# nguyenly.net
KiCad netlist of a schematic drawn in Altium Designer
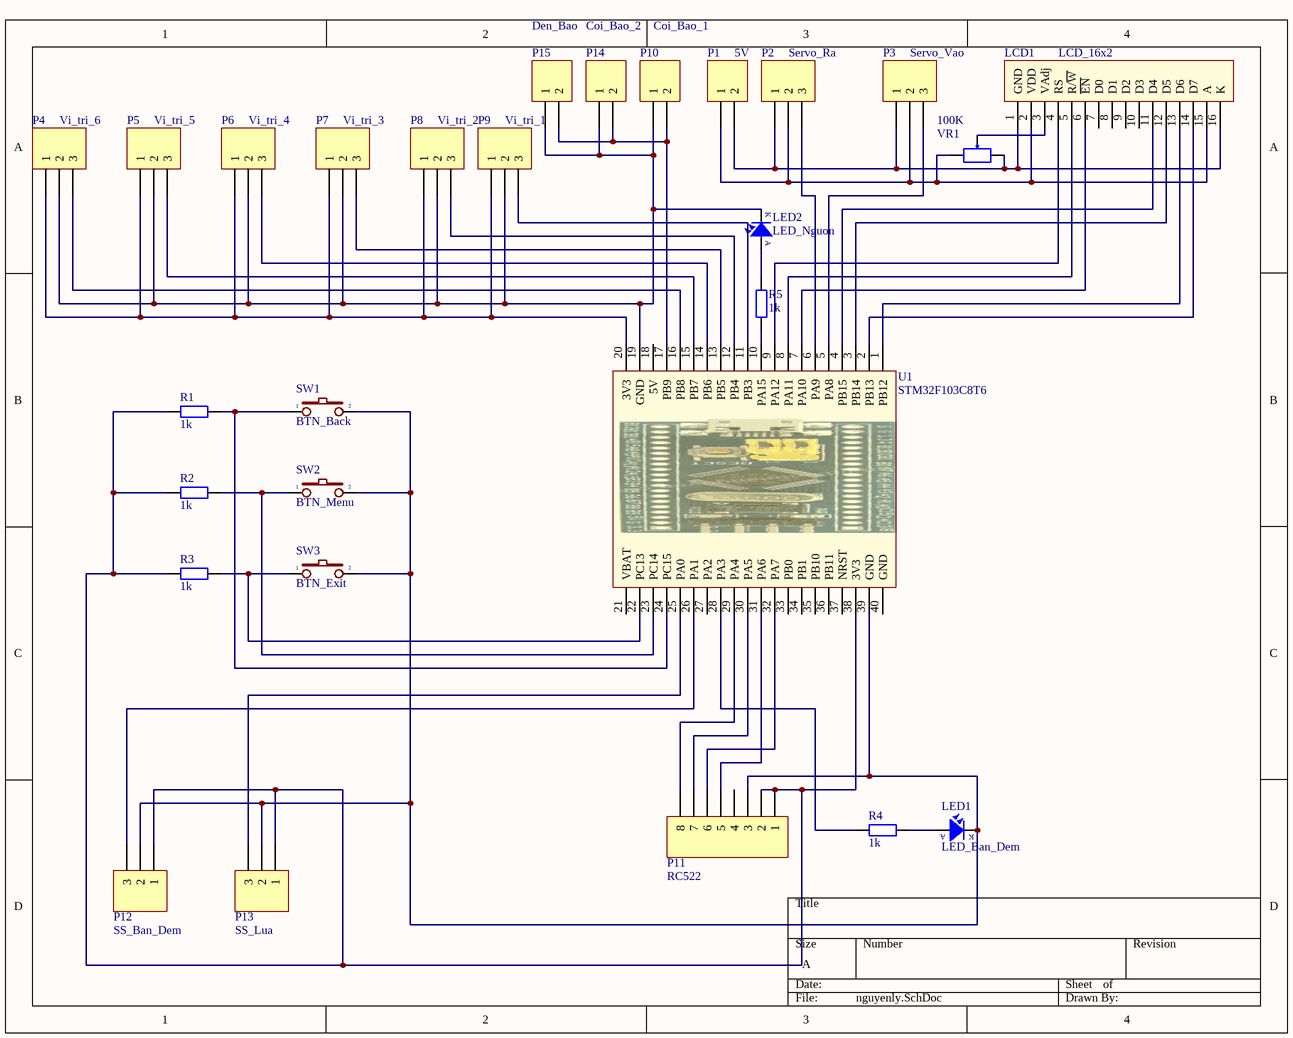
[diagram p0: nguyenly.SchDoc]

(export (version "E")
  (design (tool "Eeschema 10.0.6"))
  (components
    (comp (ref "LCD1")
      (value "LCD_16x2")
      (footprint "LCD16X2")
      (description "LCD dipslay 16 char, 2 line")
      (libsource (lib "Thu vien Altium") (part "LCD16x2"))
    )
    (comp (ref "LED1")
      (value "LED_Ban_Dem")
      (footprint "LED-5")
      (description "LED Single colour Green and Red")
      (libsource (lib "Thu vien Altium") (part "LED"))
    )
    (comp (ref "LED2")
      (value "LED_Nguon")
      (footprint "LED-5")
      (description "LED Single colour Green and Red")
      (libsource (lib "Thu vien Altium") (part "LED"))
    )
    (comp (ref "P1")
      (value "5V")
      (footprint "HDR1X2")
      (description "Header, 2-Pin")
      (fields (field (name "PUBLISHER") "Altium Limited"))
      (libsource (lib "Miscellaneous Connectors") (part "Header 2"))
    )
    (comp (ref "P2")
      (value "Servo_Ra")
      (footprint "HDR1X3")
      (description "Header, 3-Pin")
      (fields (field (name "PUBLISHER") "Altium Limited"))
      (libsource (lib "Miscellaneous Connectors") (part "Header 3"))
    )
    (comp (ref "P3")
      (value "Servo_Vao")
      (footprint "HDR1X3")
      (description "Header, 3-Pin")
      (fields (field (name "PUBLISHER") "Altium Limited"))
      (libsource (lib "Miscellaneous Connectors") (part "Header 3"))
    )
    (comp (ref "P4")
      (value "Vi_tri_6")
      (footprint "HDR1X3")
      (description "Header, 3-Pin")
      (fields (field (name "PUBLISHER") "Altium Limited"))
      (libsource (lib "Miscellaneous Connectors") (part "Header 3"))
    )
    (comp (ref "P5")
      (value "Vi_tri_5")
      (footprint "HDR1X3")
      (description "Header, 3-Pin")
      (fields (field (name "PUBLISHER") "Altium Limited"))
      (libsource (lib "Miscellaneous Connectors") (part "Header 3"))
    )
    (comp (ref "P6")
      (value "Vi_tri_4")
      (footprint "HDR1X3")
      (description "Header, 3-Pin")
      (fields (field (name "PUBLISHER") "Altium Limited"))
      (libsource (lib "Miscellaneous Connectors") (part "Header 3"))
    )
    (comp (ref "P7")
      (value "Vi_tri_3")
      (footprint "HDR1X3")
      (description "Header, 3-Pin")
      (fields (field (name "PUBLISHER") "Altium Limited"))
      (libsource (lib "Miscellaneous Connectors") (part "Header 3"))
    )
    (comp (ref "P8")
      (value "Vi_tri_2")
      (footprint "HDR1X3")
      (description "Header, 3-Pin")
      (fields (field (name "PUBLISHER") "Altium Limited"))
      (libsource (lib "Miscellaneous Connectors") (part "Header 3"))
    )
    (comp (ref "P9")
      (value "Vi_tri_1")
      (footprint "HDR1X3")
      (description "Header, 3-Pin")
      (fields (field (name "PUBLISHER") "Altium Limited"))
      (libsource (lib "Miscellaneous Connectors") (part "Header 3"))
    )
    (comp (ref "P10")
      (value "Coi_Bao_1")
      (footprint "HDR1X2")
      (description "Header, 2-Pin")
      (fields (field (name "PUBLISHER") "Altium Limited"))
      (libsource (lib "Miscellaneous Connectors") (part "Header 2"))
    )
    (comp (ref "P11")
      (value "RC522")
      (footprint "HDR1X8")
      (description "Header, 8-Pin")
      (fields (field (name "PUBLISHER") "Altium Limited"))
      (libsource (lib "Miscellaneous Connectors") (part "Header 8"))
    )
    (comp (ref "P12")
      (value "SS_Ban_Dem")
      (footprint "HDR1X3")
      (description "Header, 3-Pin")
      (fields (field (name "PUBLISHER") "Altium Limited"))
      (libsource (lib "") (part "Header 3_1"))
    )
    (comp (ref "P13")
      (value "SS_Lua")
      (footprint "HDR1X3")
      (description "Header, 3-Pin")
      (fields (field (name "PUBLISHER") "Altium Limited"))
      (libsource (lib "") (part "Header 3_1"))
    )
    (comp (ref "P14")
      (value "Coi_Bao_2")
      (footprint "HDR1X2")
      (description "Header, 2-Pin")
      (fields (field (name "PUBLISHER") "Altium Limited"))
      (libsource (lib "Miscellaneous Connectors") (part "Header 2"))
    )
    (comp (ref "P15")
      (value "Den_Bao")
      (footprint "HDR1X2")
      (description "Header, 2-Pin")
      (fields (field (name "PUBLISHER") "Altium Limited"))
      (libsource (lib "Miscellaneous Connectors") (part "Header 2"))
    )
    (comp (ref "R1")
      (value "1k")
      (footprint "R1/4W")
      (description "Resistor 1/4W")
      (libsource (lib "Thu vien Altium") (part "R1/4W"))
    )
    (comp (ref "R2")
      (value "1k")
      (footprint "R1/4W")
      (description "Resistor 1/4W")
      (libsource (lib "Thu vien Altium") (part "R1/4W"))
    )
    (comp (ref "R3")
      (value "1k")
      (footprint "R1/4W")
      (description "Resistor 1/4W")
      (libsource (lib "Thu vien Altium") (part "R1/4W"))
    )
    (comp (ref "R4")
      (value "1k")
      (footprint "R1/4W")
      (description "Resistor 1/4W")
      (libsource (lib "Thu vien Altium") (part "R1/4W"))
    )
    (comp (ref "R5")
      (value "1k")
      (footprint "R1/4W")
      (description "Resistor 1/4W")
      (libsource (lib "Thu vien Altium") (part "R1/4W"))
    )
    (comp (ref "SW1")
      (value "BTN_Back")
      (footprint "SW2")
      (description "Switch button 2 pin")
      (libsource (lib "Thu vien Altium") (part "SW2"))
    )
    (comp (ref "SW2")
      (value "BTN_Menu")
      (footprint "SW2")
      (description "Switch button 2 pin")
      (libsource (lib "Thu vien Altium") (part "SW2"))
    )
    (comp (ref "SW3")
      (value "BTN_Exit")
      (footprint "SW2")
      (description "Switch button 2 pin")
      (libsource (lib "Thu vien Altium") (part "SW2"))
    )
    (comp (ref "U1")
      (value "STM32F103C8T6")
      (footprint "STM32L103C8_mini")
      (description "STM32F103C8T6 Mini Board")
      (libsource (lib "Thu vien Altium") (part "STM32L103C8_mini"))
    )
    (comp (ref "VR1")
      (value "100K")
      (footprint "VR")
      (description "Var Resistor")
      (libsource (lib "Thu vien Altium") (part "VR"))
    )
  )
  (nets
    (net (code "1") (name "Net-(LCD1-A)") (class "Default")
      (node (ref "LCD1") (pin "15") (pinfunction "A_15") (pintype "passive"))
      (node (ref "LCD1") (pin "2") (pinfunction "VDD_2") (pintype "passive"))
      (node (ref "P1") (pin "1") (pinfunction "1_1") (pintype "passive"))
      (node (ref "P2") (pin "2") (pinfunction "2_2") (pintype "passive"))
      (node (ref "P3") (pin "2") (pinfunction "2_2") (pintype "passive"))
      (node (ref "VR1") (pin "1") (pinfunction "1_1") (pintype "passive"))
    )
    (net (code "2") (name "Net-(LCD1-D4)") (class "Default")
      (node (ref "LCD1") (pin "11") (pinfunction "D4_11") (pintype "passive"))
      (node (ref "U1") (pin "4") (pinfunction "PB15_4") (pintype "passive"))
    )
    (net (code "3") (name "Net-(LCD1-D5)") (class "Default")
      (node (ref "LCD1") (pin "12") (pinfunction "D5_12") (pintype "passive"))
      (node (ref "U1") (pin "3") (pinfunction "PB14_3") (pintype "passive"))
    )
    (net (code "4") (name "Net-(LCD1-D6)") (class "Default")
      (node (ref "LCD1") (pin "13") (pinfunction "D6_13") (pintype "passive"))
      (node (ref "U1") (pin "1") (pinfunction "PB12_1") (pintype "passive"))
    )
    (net (code "5") (name "Net-(LCD1-D7)") (class "Default")
      (node (ref "LCD1") (pin "14") (pinfunction "D7_14") (pintype "passive"))
      (node (ref "U1") (pin "2") (pinfunction "PB13_2") (pintype "passive"))
    )
    (net (code "6") (name "Net-(LCD1-GND)") (class "Default")
      (node (ref "LCD1") (pin "1") (pinfunction "GND_1") (pintype "passive"))
      (node (ref "LCD1") (pin "16") (pinfunction "K_16") (pintype "passive"))
      (node (ref "P1") (pin "2") (pinfunction "2_2") (pintype "passive"))
      (node (ref "P2") (pin "1") (pinfunction "1_1") (pintype "passive"))
      (node (ref "P3") (pin "1") (pinfunction "1_1") (pintype "passive"))
      (node (ref "VR1") (pin "3") (pinfunction "3_3") (pintype "passive"))
    )
    (net (code "7") (name "Net-(LCD1-RS)") (class "Default")
      (node (ref "LCD1") (pin "4") (pinfunction "RS_4") (pintype "passive"))
      (node (ref "U1") (pin "9") (pinfunction "PA12_9") (pintype "passive"))
    )
    (net (code "8") (name "Net-(LCD1-R{slash}~{W})") (class "Default")
      (node (ref "LCD1") (pin "5") (pinfunction "R/~{W}_5") (pintype "passive"))
      (node (ref "U1") (pin "8") (pinfunction "PA11_8") (pintype "passive"))
    )
    (net (code "9") (name "Net-(LCD1-VAdj)") (class "Default")
      (node (ref "LCD1") (pin "3") (pinfunction "VAdj_3") (pintype "passive"))
      (node (ref "VR1") (pin "2") (pinfunction "2_2") (pintype "passive"))
    )
    (net (code "10") (name "Net-(LCD1-~{EN})") (class "Default")
      (node (ref "LCD1") (pin "6") (pinfunction "~{EN}_6") (pintype "passive"))
      (node (ref "U1") (pin "7") (pinfunction "PA10_7") (pintype "passive"))
    )
    (net (code "11") (name "Net-(LED1-A)") (class "Default")
      (node (ref "LED1") (pin "1") (pinfunction "A_1") (pintype "passive"))
      (node (ref "R4") (pin "2") (pinfunction "2_2") (pintype "passive"))
    )
    (net (code "12") (name "Net-(LED1-K)") (class "Default")
      (node (ref "LED1") (pin "2") (pinfunction "K_2") (pintype "passive"))
      (node (ref "P11") (pin "3") (pinfunction "3_3") (pintype "passive"))
      (node (ref "P12") (pin "2") (pinfunction "2_2") (pintype "passive"))
      (node (ref "P13") (pin "2") (pinfunction "2_2") (pintype "passive"))
      (node (ref "SW1") (pin "2") (pinfunction "2_2") (pintype "passive"))
      (node (ref "SW2") (pin "2") (pinfunction "2_2") (pintype "passive"))
      (node (ref "SW3") (pin "2") (pinfunction "2_2") (pintype "passive"))
      (node (ref "U1") (pin "39") (pinfunction "GND_39") (pintype "passive"))
    )
    (net (code "13") (name "Net-(LED2-A)") (class "Default")
      (node (ref "LED2") (pin "1") (pinfunction "A_1") (pintype "passive"))
      (node (ref "R5") (pin "2") (pinfunction "2_2") (pintype "passive"))
    )
    (net (code "14") (name "Net-(LED2-K)") (class "Default")
      (node (ref "LED2") (pin "2") (pinfunction "K_2") (pintype "passive"))
      (node (ref "P10") (pin "1") (pinfunction "1_1") (pintype "passive"))
      (node (ref "P14") (pin "1") (pinfunction "1_1") (pintype "passive"))
      (node (ref "P15") (pin "1") (pinfunction "1_1") (pintype "passive"))
      (node (ref "P4") (pin "2") (pinfunction "2_2") (pintype "passive"))
      (node (ref "P5") (pin "2") (pinfunction "2_2") (pintype "passive"))
      (node (ref "P6") (pin "2") (pinfunction "2_2") (pintype "passive"))
      (node (ref "P7") (pin "2") (pinfunction "2_2") (pintype "passive"))
      (node (ref "P8") (pin "2") (pinfunction "2_2") (pintype "passive"))
      (node (ref "P9") (pin "2") (pinfunction "2_2") (pintype "passive"))
      (node (ref "U1") (pin "19") (pinfunction "GND_19") (pintype "passive"))
    )
    (net (code "15") (name "Net-(P4-Pad1)") (class "Default")
      (node (ref "P4") (pin "1") (pinfunction "1_1") (pintype "passive"))
      (node (ref "P5") (pin "1") (pinfunction "1_1") (pintype "passive"))
      (node (ref "P6") (pin "1") (pinfunction "1_1") (pintype "passive"))
      (node (ref "P7") (pin "1") (pinfunction "1_1") (pintype "passive"))
      (node (ref "P8") (pin "1") (pinfunction "1_1") (pintype "passive"))
      (node (ref "P9") (pin "1") (pinfunction "1_1") (pintype "passive"))
      (node (ref "U1") (pin "20") (pinfunction "3V3_20") (pintype "passive"))
    )
    (net (code "16") (name "Net-(P11-Pad1)") (class "Default")
      (node (ref "P11") (pin "1") (pinfunction "1_1") (pintype "passive"))
      (node (ref "P11") (pin "2") (pinfunction "2_2") (pintype "passive"))
      (node (ref "P12") (pin "1") (pinfunction "1_1") (pintype "passive"))
      (node (ref "P13") (pin "1") (pinfunction "1_1") (pintype "passive"))
      (node (ref "R1") (pin "1") (pinfunction "1_1") (pintype "passive"))
      (node (ref "R2") (pin "1") (pinfunction "1_1") (pintype "passive"))
      (node (ref "R3") (pin "1") (pinfunction "1_1") (pintype "passive"))
      (node (ref "U1") (pin "38") (pinfunction "3V3_38") (pintype "passive"))
    )
    (net (code "17") (name "Net-(U1-PA0)") (class "Default")
      (node (ref "P13") (pin "3") (pinfunction "3_3") (pintype "passive"))
      (node (ref "U1") (pin "25") (pinfunction "PA0_25") (pintype "passive"))
    )
    (net (code "18") (name "Net-(U1-PA1)") (class "Default")
      (node (ref "P12") (pin "3") (pinfunction "3_3") (pintype "passive"))
      (node (ref "U1") (pin "26") (pinfunction "PA1_26") (pintype "passive"))
    )
    (net (code "19") (name "Net-(U1-PA3)") (class "Default")
      (node (ref "R4") (pin "1") (pinfunction "1_1") (pintype "passive"))
      (node (ref "U1") (pin "28") (pinfunction "PA3_28") (pintype "passive"))
    )
    (net (code "20") (name "Net-(U1-PA4)") (class "Default")
      (node (ref "P11") (pin "8") (pinfunction "8_8") (pintype "passive"))
      (node (ref "U1") (pin "29") (pinfunction "PA4_29") (pintype "passive"))
    )
    (net (code "21") (name "Net-(U1-PA5)") (class "Default")
      (node (ref "P11") (pin "7") (pinfunction "7_7") (pintype "passive"))
      (node (ref "U1") (pin "30") (pinfunction "PA5_30") (pintype "passive"))
    )
    (net (code "22") (name "Net-(U1-PA6)") (class "Default")
      (node (ref "P11") (pin "5") (pinfunction "5_5") (pintype "passive"))
      (node (ref "U1") (pin "31") (pinfunction "PA6_31") (pintype "passive"))
    )
    (net (code "23") (name "Net-(U1-PA7)") (class "Default")
      (node (ref "P11") (pin "6") (pinfunction "6_6") (pintype "passive"))
      (node (ref "U1") (pin "32") (pinfunction "PA7_32") (pintype "passive"))
    )
    (net (code "24") (name "Net-(U1-PA8)") (class "Default")
      (node (ref "P3") (pin "3") (pinfunction "3_3") (pintype "passive"))
      (node (ref "U1") (pin "5") (pinfunction "PA8_5") (pintype "passive"))
    )
    (net (code "25") (name "Net-(U1-PA9)") (class "Default")
      (node (ref "P2") (pin "3") (pinfunction "3_3") (pintype "passive"))
      (node (ref "U1") (pin "6") (pinfunction "PA9_6") (pintype "passive"))
    )
    (net (code "26") (name "Net-(U1-PA15)") (class "Default")
      (node (ref "R5") (pin "1") (pinfunction "1_1") (pintype "passive"))
      (node (ref "U1") (pin "10") (pinfunction "PA15_10") (pintype "passive"))
    )
    (net (code "27") (name "Net-(U1-PB3)") (class "Default")
      (node (ref "P9") (pin "3") (pinfunction "3_3") (pintype "passive"))
      (node (ref "U1") (pin "11") (pinfunction "PB3_11") (pintype "passive"))
    )
    (net (code "28") (name "Net-(U1-PB4)") (class "Default")
      (node (ref "P8") (pin "3") (pinfunction "3_3") (pintype "passive"))
      (node (ref "U1") (pin "12") (pinfunction "PB4_12") (pintype "passive"))
    )
    (net (code "29") (name "Net-(U1-PB5)") (class "Default")
      (node (ref "P7") (pin "3") (pinfunction "3_3") (pintype "passive"))
      (node (ref "U1") (pin "13") (pinfunction "PB5_13") (pintype "passive"))
    )
    (net (code "30") (name "Net-(U1-PB6)") (class "Default")
      (node (ref "P6") (pin "3") (pinfunction "3_3") (pintype "passive"))
      (node (ref "U1") (pin "14") (pinfunction "PB6_14") (pintype "passive"))
    )
    (net (code "31") (name "Net-(U1-PB7)") (class "Default")
      (node (ref "P5") (pin "3") (pinfunction "3_3") (pintype "passive"))
      (node (ref "U1") (pin "15") (pinfunction "PB7_15") (pintype "passive"))
    )
    (net (code "32") (name "Net-(U1-PB8)") (class "Default")
      (node (ref "P4") (pin "3") (pinfunction "3_3") (pintype "passive"))
      (node (ref "U1") (pin "16") (pinfunction "PB8_16") (pintype "passive"))
    )
    (net (code "33") (name "Net-(U1-PB9)") (class "Default")
      (node (ref "P10") (pin "2") (pinfunction "2_2") (pintype "passive"))
      (node (ref "P14") (pin "2") (pinfunction "2_2") (pintype "passive"))
      (node (ref "P15") (pin "2") (pinfunction "2_2") (pintype "passive"))
      (node (ref "U1") (pin "17") (pinfunction "PB9_17") (pintype "passive"))
    )
    (net (code "34") (name "Net-(U1-PC13)") (class "Default")
      (node (ref "R3") (pin "2") (pinfunction "2_2") (pintype "passive"))
      (node (ref "SW3") (pin "1") (pinfunction "1_1") (pintype "passive"))
      (node (ref "U1") (pin "22") (pinfunction "PC13_22") (pintype "passive"))
    )
    (net (code "35") (name "Net-(U1-PC14)") (class "Default")
      (node (ref "R2") (pin "2") (pinfunction "2_2") (pintype "passive"))
      (node (ref "SW2") (pin "1") (pinfunction "1_1") (pintype "passive"))
      (node (ref "U1") (pin "23") (pinfunction "PC14_23") (pintype "passive"))
    )
    (net (code "36") (name "Net-(U1-PC15)") (class "Default")
      (node (ref "R1") (pin "2") (pinfunction "2_2") (pintype "passive"))
      (node (ref "SW1") (pin "1") (pinfunction "1_1") (pintype "passive"))
      (node (ref "U1") (pin "24") (pinfunction "PC15_24") (pintype "passive"))
    )
    (net (code "37") (name "unconnected-(LCD1-D0-Pad7)") (class "Default")
      (node (ref "LCD1") (pin "7") (pinfunction "D0_7") (pintype "passive"))
    )
    (net (code "38") (name "unconnected-(LCD1-D1-Pad8)") (class "Default")
      (node (ref "LCD1") (pin "8") (pinfunction "D1_8") (pintype "passive"))
    )
    (net (code "39") (name "unconnected-(LCD1-D2-Pad9)") (class "Default")
      (node (ref "LCD1") (pin "9") (pinfunction "D2_9") (pintype "passive"))
    )
    (net (code "40") (name "unconnected-(LCD1-D3-Pad10)") (class "Default")
      (node (ref "LCD1") (pin "10") (pinfunction "D3_10") (pintype "passive"))
    )
    (net (code "41") (name "unconnected-(P11-Pad4)") (class "Default")
      (node (ref "P11") (pin "4") (pinfunction "4_4") (pintype "passive"))
    )
    (net (code "42") (name "unconnected-(U1-5V-Pad18)") (class "Default")
      (node (ref "U1") (pin "18") (pinfunction "5V_18") (pintype "passive"))
    )
    (net (code "43") (name "unconnected-(U1-GND-Pad40)") (class "Default")
      (node (ref "U1") (pin "40") (pinfunction "GND_40") (pintype "passive"))
    )
    (net (code "44") (name "unconnected-(U1-NRST-Pad37)") (class "Default")
      (node (ref "U1") (pin "37") (pinfunction "NRST_37") (pintype "passive"))
    )
    (net (code "45") (name "unconnected-(U1-PA2-Pad27)") (class "Default")
      (node (ref "U1") (pin "27") (pinfunction "PA2_27") (pintype "passive"))
    )
    (net (code "46") (name "unconnected-(U1-PB0-Pad33)") (class "Default")
      (node (ref "U1") (pin "33") (pinfunction "PB0_33") (pintype "passive"))
    )
    (net (code "47") (name "unconnected-(U1-PB1-Pad34)") (class "Default")
      (node (ref "U1") (pin "34") (pinfunction "PB1_34") (pintype "passive"))
    )
    (net (code "48") (name "unconnected-(U1-PB10-Pad35)") (class "Default")
      (node (ref "U1") (pin "35") (pinfunction "PB10_35") (pintype "passive"))
    )
    (net (code "49") (name "unconnected-(U1-PB11-Pad36)") (class "Default")
      (node (ref "U1") (pin "36") (pinfunction "PB11_36") (pintype "passive"))
    )
    (net (code "50") (name "unconnected-(U1-VBAT-Pad21)") (class "Default")
      (node (ref "U1") (pin "21") (pinfunction "VBAT_21") (pintype "passive"))
    )
  )
)
